# poe_injector.net
KiCad netlist of a schematic drawn in EAGLE
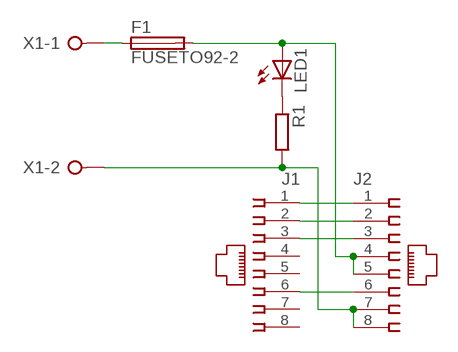
[diagram p0: schematic, sheet 1]

(export (version "E")
  (design (tool "Eeschema 10.0.6"))
  (components
    (comp (ref "F1")
      (value "FUSETO92-2")
      (footprint "eagle-import:TO92-2")
      (libsource (lib "eagle-import") (part "FUSETO92-2"))
    )
    (comp (ref "J1")
      (value "520251-4")
      (footprint "eagle-import:520251-4")
      (libsource (lib "eagle-import") (part "520251-4"))
    )
    (comp (ref "J2")
      (value "520251-4")
      (footprint "eagle-import:520251-4")
      (libsource (lib "eagle-import") (part "520251-4"))
    )
    (comp (ref "LED1")
      (value "LED3MM")
      (footprint "eagle-import:LED3MM")
      (libsource (lib "eagle-import") (part "LED3MM"))
    )
    (comp (ref "R1")
      (value "R-EU_0207/10")
      (footprint "eagle-import:0207_10")
      (libsource (lib "eagle-import") (part "R-EU_0207/10"))
    )
    (comp (ref "X1")
      (value "W237-02P")
      (footprint "eagle-import:W237-132")
      (libsource (lib "eagle-import") (part "W237-02P"))
    )
  )
  (nets
    (net (code "1") (name "Net-(F1-2)") (class "Default")
      (node (ref "F1") (pin "3") (pinfunction "2_3") (pintype "passive"))
      (node (ref "J2") (pin "4") (pinfunction "4_4") (pintype "passive"))
      (node (ref "J2") (pin "5") (pinfunction "5_5") (pintype "passive"))
      (node (ref "LED1") (pin "A") (pinfunction "A_A") (pintype "passive"))
    )
    (net (code "2") (name "Net-(J1-Pad1)") (class "Default")
      (node (ref "J1") (pin "1") (pinfunction "1_1") (pintype "passive"))
      (node (ref "J2") (pin "1") (pinfunction "1_1") (pintype "passive"))
    )
    (net (code "3") (name "Net-(J1-Pad2)") (class "Default")
      (node (ref "J1") (pin "2") (pinfunction "2_2") (pintype "passive"))
      (node (ref "J2") (pin "2") (pinfunction "2_2") (pintype "passive"))
    )
    (net (code "4") (name "Net-(J1-Pad3)") (class "Default")
      (node (ref "J1") (pin "3") (pinfunction "3_3") (pintype "passive"))
      (node (ref "J2") (pin "3") (pinfunction "3_3") (pintype "passive"))
    )
    (net (code "5") (name "Net-(J1-Pad6)") (class "Default")
      (node (ref "J1") (pin "6") (pinfunction "6_6") (pintype "passive"))
      (node (ref "J2") (pin "6") (pinfunction "6_6") (pintype "passive"))
    )
    (net (code "6") (name "Net-(LED1-C)") (class "Default")
      (node (ref "LED1") (pin "K") (pinfunction "C_K") (pintype "passive"))
      (node (ref "R1") (pin "1") (pinfunction "1_1") (pintype "passive"))
    )
    (net (code "7") (name "Net-(X1A-KL)") (class "Default")
      (node (ref "F1") (pin "1") (pinfunction "1_1") (pintype "passive"))
      (node (ref "X1") (pin "1") (pinfunction "KL_1") (pintype "passive"))
    )
    (net (code "8") (name "Net-(X1B-KL)") (class "Default")
      (node (ref "J2") (pin "7") (pinfunction "7_7") (pintype "passive"))
      (node (ref "J2") (pin "8") (pinfunction "8_8") (pintype "passive"))
      (node (ref "R1") (pin "2") (pinfunction "2_2") (pintype "passive"))
      (node (ref "X1") (pin "2") (pinfunction "KL_2") (pintype "passive"))
    )
    (net (code "9") (name "unconnected-(J1-Pad4)") (class "Default")
      (node (ref "J1") (pin "4") (pinfunction "4_4") (pintype "passive"))
    )
    (net (code "10") (name "unconnected-(J1-Pad5)") (class "Default")
      (node (ref "J1") (pin "5") (pinfunction "5_5") (pintype "passive"))
    )
    (net (code "11") (name "unconnected-(J1-Pad7)") (class "Default")
      (node (ref "J1") (pin "7") (pinfunction "7_7") (pintype "passive"))
    )
    (net (code "12") (name "unconnected-(J1-Pad8)") (class "Default")
      (node (ref "J1") (pin "8") (pinfunction "8_8") (pintype "passive"))
    )
  )
)
